# SV60mAHelleLEDs.net
KiCad netlist of a schematic drawn in EAGLE
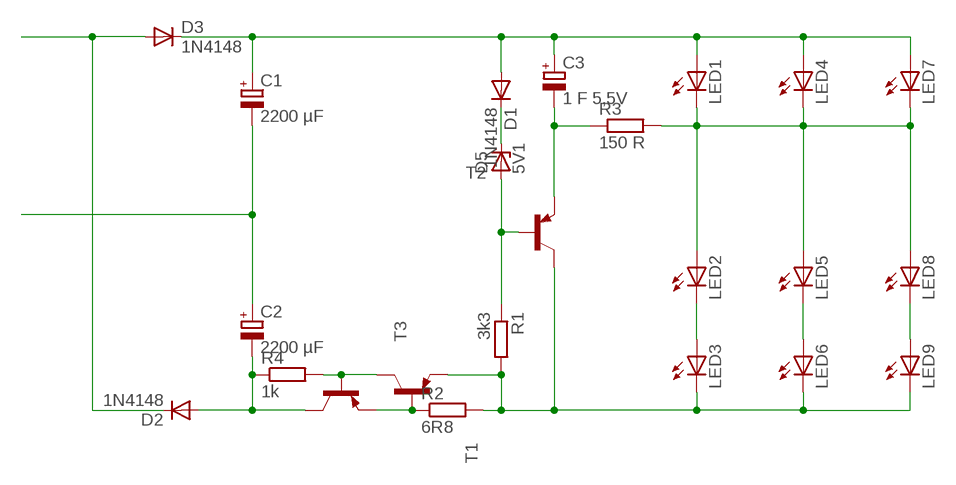
[diagram p0: schematic, sheet 1]

(export (version "E")
  (design (tool "Eeschema 10.0.6"))
  (components
    (comp (ref "C1")
      (value "2200 µF")
      (footprint "eagle-import:E5-10,5")
      (libsource (lib "eagle-import") (part "CPOL-EUE5-10.5"))
    )
    (comp (ref "C2")
      (value "2200 µF")
      (footprint "eagle-import:E5-10,5")
      (libsource (lib "eagle-import") (part "CPOL-EUE5-10.5"))
    )
    (comp (ref "C3")
      (value "1 F 5,5V")
      (footprint "eagle-import:E3,5-10")
      (libsource (lib "eagle-import") (part "CPOL-EUE3.5-10"))
    )
    (comp (ref "D1")
      (value "1N4148")
      (footprint "eagle-import:DO35-10")
      (libsource (lib "eagle-import") (part "1N4148DO35-10"))
    )
    (comp (ref "D2")
      (value "1N4148")
      (footprint "eagle-import:DO35-10")
      (libsource (lib "eagle-import") (part "1N4148DO35-10"))
    )
    (comp (ref "D3")
      (value "1N4148")
      (footprint "eagle-import:DO35-10")
      (libsource (lib "eagle-import") (part "1N4148DO35-10"))
    )
    (comp (ref "D5")
      (value "5V1")
      (footprint "eagle-import:SOD81")
      (libsource (lib "eagle-import") (part "BZD23"))
    )
    (comp (ref "LED1")
      (value "LED5MM")
      (footprint "eagle-import:LED5MM")
      (libsource (lib "eagle-import") (part "LED5MM"))
    )
    (comp (ref "LED2")
      (value "LED5MM")
      (footprint "eagle-import:LED5MM")
      (libsource (lib "eagle-import") (part "LED5MM"))
    )
    (comp (ref "LED3")
      (value "LED5MM")
      (footprint "eagle-import:LED5MM")
      (libsource (lib "eagle-import") (part "LED5MM"))
    )
    (comp (ref "LED4")
      (value "LED5MM")
      (footprint "eagle-import:LED5MM")
      (libsource (lib "eagle-import") (part "LED5MM"))
    )
    (comp (ref "LED5")
      (value "LED5MM")
      (footprint "eagle-import:LED5MM")
      (libsource (lib "eagle-import") (part "LED5MM"))
    )
    (comp (ref "LED6")
      (value "LED5MM")
      (footprint "eagle-import:LED5MM")
      (libsource (lib "eagle-import") (part "LED5MM"))
    )
    (comp (ref "LED7")
      (value "LED5MM")
      (footprint "eagle-import:LED5MM")
      (libsource (lib "eagle-import") (part "LED5MM"))
    )
    (comp (ref "LED8")
      (value "LED5MM")
      (footprint "eagle-import:LED5MM")
      (libsource (lib "eagle-import") (part "LED5MM"))
    )
    (comp (ref "LED9")
      (value "LED5MM")
      (footprint "eagle-import:LED5MM")
      (libsource (lib "eagle-import") (part "LED5MM"))
    )
    (comp (ref "R1")
      (value "3k3")
      (footprint "eagle-import:0207_10")
      (libsource (lib "eagle-import") (part "R-EU_0207/10"))
    )
    (comp (ref "R2")
      (value "6R8")
      (footprint "eagle-import:0207_10")
      (libsource (lib "eagle-import") (part "R-EU_0207/10"))
    )
    (comp (ref "R3")
      (value "150 R")
      (footprint "eagle-import:0207_10")
      (libsource (lib "eagle-import") (part "R-EU_0207/10"))
    )
    (comp (ref "R4")
      (value "1k")
      (footprint "eagle-import:0207_10")
      (libsource (lib "eagle-import") (part "R-EU_0207/10"))
    )
    (comp (ref "T1")
      (value "2N2907-PNP-TO18-EBC")
      (footprint "eagle-import:TO18")
      (libsource (lib "eagle-import") (part "-PNP-TO18-EBC2N2907"))
    )
    (comp (ref "T2")
      (value "2N2907-PNP-TO18-EBC")
      (footprint "eagle-import:TO18")
      (libsource (lib "eagle-import") (part "-PNP-TO18-EBC2N2907"))
    )
    (comp (ref "T3")
      (value "2N2907-PNP-TO18-EBC")
      (footprint "eagle-import:TO18")
      (libsource (lib "eagle-import") (part "-PNP-TO18-EBC2N2907"))
    )
  )
  (nets
    (net (code "1") (name "Net-(C1-Pad+)") (class "Default")
      (node (ref "C1") (pin "+") (pinfunction "+_+") (pintype "passive"))
      (node (ref "C3") (pin "+") (pinfunction "+_+") (pintype "passive"))
      (node (ref "D1") (pin "A") (pinfunction "A_A") (pintype "passive"))
      (node (ref "D3") (pin "C") (pinfunction "C_C") (pintype "passive"))
      (node (ref "LED1") (pin "A") (pinfunction "A_A") (pintype "passive"))
      (node (ref "LED4") (pin "A") (pinfunction "A_A") (pintype "passive"))
      (node (ref "LED7") (pin "A") (pinfunction "A_A") (pintype "passive"))
    )
    (net (code "2") (name "Net-(C1-Pad-)") (class "Default")
      (node (ref "C1") (pin "-") (pinfunction "-_-") (pintype "passive"))
      (node (ref "C2") (pin "+") (pinfunction "+_+") (pintype "passive"))
    )
    (net (code "3") (name "Net-(D1-PadC)") (class "Default")
      (node (ref "D1") (pin "C") (pinfunction "C_C") (pintype "passive"))
      (node (ref "D5") (pin "C") (pinfunction "C_C") (pintype "passive"))
    )
    (net (code "4") (name "Net-(D2-PadC)") (class "Default")
      (node (ref "D2") (pin "C") (pinfunction "C_C") (pintype "passive"))
      (node (ref "D3") (pin "A") (pinfunction "A_A") (pintype "passive"))
    )
    (net (code "5") (name "Net-(LED1-C)") (class "Default")
      (node (ref "LED1") (pin "K") (pinfunction "C_K") (pintype "passive"))
      (node (ref "LED2") (pin "A") (pinfunction "A_A") (pintype "passive"))
      (node (ref "LED4") (pin "K") (pinfunction "C_K") (pintype "passive"))
      (node (ref "LED5") (pin "A") (pinfunction "A_A") (pintype "passive"))
      (node (ref "LED7") (pin "K") (pinfunction "C_K") (pintype "passive"))
      (node (ref "LED8") (pin "A") (pinfunction "A_A") (pintype "passive"))
      (node (ref "R3") (pin "2") (pinfunction "2_2") (pintype "passive"))
    )
    (net (code "6") (name "Net-(LED2-C)") (class "Default")
      (node (ref "LED2") (pin "K") (pinfunction "C_K") (pintype "passive"))
      (node (ref "LED3") (pin "A") (pinfunction "A_A") (pintype "passive"))
    )
    (net (code "7") (name "Net-(LED3-C)") (class "Default")
      (node (ref "LED3") (pin "K") (pinfunction "C_K") (pintype "passive"))
      (node (ref "LED6") (pin "K") (pinfunction "C_K") (pintype "passive"))
      (node (ref "LED9") (pin "K") (pinfunction "C_K") (pintype "passive"))
      (node (ref "R1") (pin "2") (pinfunction "2_2") (pintype "passive"))
      (node (ref "R2") (pin "2") (pinfunction "2_2") (pintype "passive"))
      (node (ref "T1") (pin "1") (pinfunction "E_1") (pintype "passive"))
      (node (ref "T2") (pin "3") (pinfunction "C_3") (pintype "passive"))
    )
    (net (code "8") (name "Net-(LED5-C)") (class "Default")
      (node (ref "LED5") (pin "K") (pinfunction "C_K") (pintype "passive"))
      (node (ref "LED6") (pin "A") (pinfunction "A_A") (pintype "passive"))
    )
    (net (code "9") (name "Net-(LED8-C)") (class "Default")
      (node (ref "LED8") (pin "K") (pinfunction "C_K") (pintype "passive"))
      (node (ref "LED9") (pin "A") (pinfunction "A_A") (pintype "passive"))
    )
    (net (code "10") (name "Net-(T1-B)") (class "Default")
      (node (ref "R2") (pin "1") (pinfunction "1_1") (pintype "passive"))
      (node (ref "T1") (pin "2") (pinfunction "B_2") (pintype "passive"))
      (node (ref "T3") (pin "1") (pinfunction "E_1") (pintype "passive"))
    )
    (net (code "11") (name "Net-(T1-C)") (class "Default")
      (node (ref "R4") (pin "2") (pinfunction "2_2") (pintype "passive"))
      (node (ref "T1") (pin "3") (pinfunction "C_3") (pintype "passive"))
      (node (ref "T3") (pin "2") (pinfunction "B_2") (pintype "passive"))
    )
    (net (code "12") (name "Net-(T2-B)") (class "Default")
      (node (ref "D5") (pin "A") (pinfunction "A_A") (pintype "passive"))
      (node (ref "R1") (pin "1") (pinfunction "1_1") (pintype "passive"))
      (node (ref "T2") (pin "2") (pinfunction "B_2") (pintype "passive"))
    )
    (net (code "13") (name "Net-(T2-E)") (class "Default")
      (node (ref "C3") (pin "-") (pinfunction "-_-") (pintype "passive"))
      (node (ref "R3") (pin "1") (pinfunction "1_1") (pintype "passive"))
      (node (ref "T2") (pin "1") (pinfunction "E_1") (pintype "passive"))
    )
    (net (code "14") (name "Net-(T3-C)") (class "Default")
      (node (ref "C2") (pin "-") (pinfunction "-_-") (pintype "passive"))
      (node (ref "D2") (pin "A") (pinfunction "A_A") (pintype "passive"))
      (node (ref "R4") (pin "1") (pinfunction "1_1") (pintype "passive"))
      (node (ref "T3") (pin "3") (pinfunction "C_3") (pintype "passive"))
    )
  )
)
